# socket.net
KiCad netlist of a schematic drawn in Altium Designer
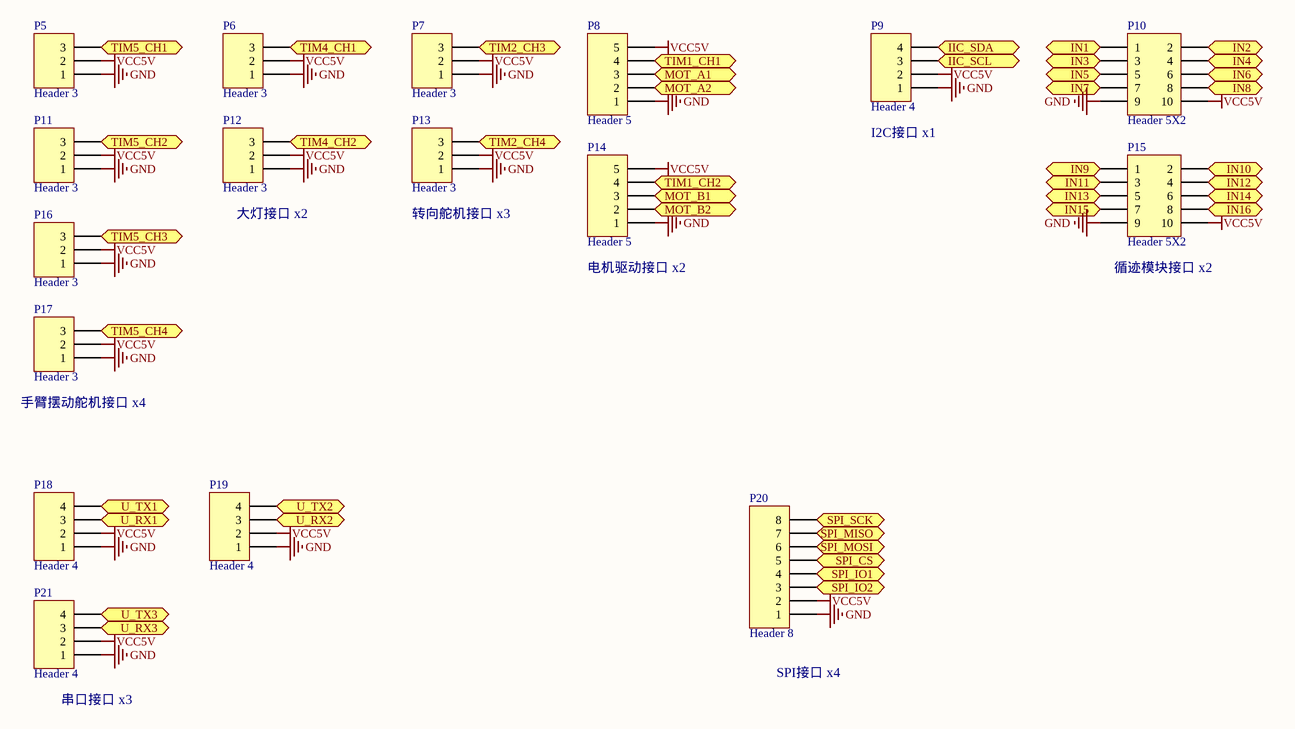
[diagram p0: socket.SchDoc]

(export (version "E")
  (design (tool "Eeschema 10.0.6"))
  (components
    (comp (ref "P5")
      (value "Header 3")
      (footprint "HDR1X3")
      (description "Header, 3-Pin")
      (fields (field (name "PUBLISHER") "Altium Limited"))
      (libsource (lib "Miscellaneous Connectors") (part "Header 3"))
    )
    (comp (ref "P6")
      (value "Header 3")
      (footprint "HDR1X3")
      (description "Header, 3-Pin")
      (fields (field (name "PUBLISHER") "Altium Limited"))
      (libsource (lib "Miscellaneous Connectors") (part "Header 3"))
    )
    (comp (ref "P7")
      (value "Header 3")
      (footprint "HDR1X3")
      (description "Header, 3-Pin")
      (fields (field (name "PUBLISHER") "Altium Limited"))
      (libsource (lib "Miscellaneous Connectors") (part "Header 3"))
    )
    (comp (ref "P8")
      (value "Header 5")
      (footprint "HDR1X5")
      (description "Header, 5-Pin")
      (fields (field (name "PUBLISHER") "Altium Limited"))
      (libsource (lib "Miscellaneous Connectors") (part "Header 5"))
    )
    (comp (ref "P9")
      (value "Header 4")
      (footprint "HDR1X4")
      (description "Header, 4-Pin")
      (fields (field (name "PUBLISHER") "Altium Limited"))
      (libsource (lib "Miscellaneous Connectors") (part "Header 4"))
    )
    (comp (ref "P10")
      (value "Header 5X2")
      (footprint "HDR2X5")
      (description "Header, 5-Pin, Dual row")
      (fields (field (name "PUBLISHER") "Altium Limited"))
      (libsource (lib "Miscellaneous Connectors") (part "Header 5X2"))
    )
    (comp (ref "P11")
      (value "Header 3")
      (footprint "HDR1X3")
      (description "Header, 3-Pin")
      (fields (field (name "PUBLISHER") "Altium Limited"))
      (libsource (lib "Miscellaneous Connectors") (part "Header 3"))
    )
    (comp (ref "P12")
      (value "Header 3")
      (footprint "HDR1X3")
      (description "Header, 3-Pin")
      (fields (field (name "PUBLISHER") "Altium Limited"))
      (libsource (lib "Miscellaneous Connectors") (part "Header 3"))
    )
    (comp (ref "P13")
      (value "Header 3")
      (footprint "HDR1X3")
      (description "Header, 3-Pin")
      (fields (field (name "PUBLISHER") "Altium Limited"))
      (libsource (lib "Miscellaneous Connectors") (part "Header 3"))
    )
    (comp (ref "P14")
      (value "Header 5")
      (footprint "HDR1X5")
      (description "Header, 5-Pin")
      (fields (field (name "PUBLISHER") "Altium Limited"))
      (libsource (lib "Miscellaneous Connectors") (part "Header 5"))
    )
    (comp (ref "P15")
      (value "Header 5X2")
      (footprint "HDR2X5")
      (description "Header, 5-Pin, Dual row")
      (fields (field (name "PUBLISHER") "Altium Limited"))
      (libsource (lib "Miscellaneous Connectors") (part "Header 5X2"))
    )
    (comp (ref "P16")
      (value "Header 3")
      (footprint "HDR1X3")
      (description "Header, 3-Pin")
      (fields (field (name "PUBLISHER") "Altium Limited"))
      (libsource (lib "Miscellaneous Connectors") (part "Header 3"))
    )
    (comp (ref "P17")
      (value "Header 3")
      (footprint "HDR1X3")
      (description "Header, 3-Pin")
      (fields (field (name "PUBLISHER") "Altium Limited"))
      (libsource (lib "Miscellaneous Connectors") (part "Header 3"))
    )
    (comp (ref "P18")
      (value "Header 4")
      (footprint "HDR1X4")
      (description "Header, 4-Pin")
      (fields (field (name "PUBLISHER") "Altium Limited"))
      (libsource (lib "Miscellaneous Connectors") (part "Header 4"))
    )
    (comp (ref "P19")
      (value "Header 4")
      (footprint "HDR1X4")
      (description "Header, 4-Pin")
      (fields (field (name "PUBLISHER") "Altium Limited"))
      (libsource (lib "Miscellaneous Connectors") (part "Header 4"))
    )
    (comp (ref "P20")
      (value "Header 8")
      (footprint "HDR1X8")
      (description "Header, 8-Pin")
      (fields (field (name "PUBLISHER") "Altium Limited"))
      (libsource (lib "Miscellaneous Connectors") (part "Header 8"))
    )
    (comp (ref "P21")
      (value "Header 4")
      (footprint "HDR1X4")
      (description "Header, 4-Pin")
      (fields (field (name "PUBLISHER") "Altium Limited"))
      (libsource (lib "Miscellaneous Connectors") (part "Header 4"))
    )
  )
  (nets
    (net (code "1") (name "/IIC_SCL") (class "Default")
      (node (ref "P9") (pin "3") (pinfunction "3_3") (pintype "passive"))
    )
    (net (code "2") (name "/IIC_SDA") (class "Default")
      (node (ref "P9") (pin "4") (pinfunction "4_4") (pintype "passive"))
    )
    (net (code "3") (name "/IN1") (class "Default")
      (node (ref "P10") (pin "1") (pinfunction "1_1") (pintype "passive"))
    )
    (net (code "4") (name "/IN2") (class "Default")
      (node (ref "P10") (pin "2") (pinfunction "2_2") (pintype "passive"))
    )
    (net (code "5") (name "/IN3") (class "Default")
      (node (ref "P10") (pin "3") (pinfunction "3_3") (pintype "passive"))
    )
    (net (code "6") (name "/IN4") (class "Default")
      (node (ref "P10") (pin "4") (pinfunction "4_4") (pintype "passive"))
    )
    (net (code "7") (name "/IN5") (class "Default")
      (node (ref "P10") (pin "5") (pinfunction "5_5") (pintype "passive"))
    )
    (net (code "8") (name "/IN6") (class "Default")
      (node (ref "P10") (pin "6") (pinfunction "6_6") (pintype "passive"))
    )
    (net (code "9") (name "/IN7") (class "Default")
      (node (ref "P10") (pin "7") (pinfunction "7_7") (pintype "passive"))
    )
    (net (code "10") (name "/IN8") (class "Default")
      (node (ref "P10") (pin "8") (pinfunction "8_8") (pintype "passive"))
    )
    (net (code "11") (name "/IN9") (class "Default")
      (node (ref "P15") (pin "1") (pinfunction "1_1") (pintype "passive"))
    )
    (net (code "12") (name "/IN10") (class "Default")
      (node (ref "P15") (pin "2") (pinfunction "2_2") (pintype "passive"))
    )
    (net (code "13") (name "/IN11") (class "Default")
      (node (ref "P15") (pin "3") (pinfunction "3_3") (pintype "passive"))
    )
    (net (code "14") (name "/IN12") (class "Default")
      (node (ref "P15") (pin "4") (pinfunction "4_4") (pintype "passive"))
    )
    (net (code "15") (name "/IN13") (class "Default")
      (node (ref "P15") (pin "5") (pinfunction "5_5") (pintype "passive"))
    )
    (net (code "16") (name "/IN14") (class "Default")
      (node (ref "P15") (pin "6") (pinfunction "6_6") (pintype "passive"))
    )
    (net (code "17") (name "/IN15") (class "Default")
      (node (ref "P15") (pin "7") (pinfunction "7_7") (pintype "passive"))
    )
    (net (code "18") (name "/IN16") (class "Default")
      (node (ref "P15") (pin "8") (pinfunction "8_8") (pintype "passive"))
    )
    (net (code "19") (name "/MOT_A1") (class "Default")
      (node (ref "P8") (pin "3") (pinfunction "3_3") (pintype "passive"))
    )
    (net (code "20") (name "/MOT_A2") (class "Default")
      (node (ref "P8") (pin "2") (pinfunction "2_2") (pintype "passive"))
    )
    (net (code "21") (name "/MOT_B1") (class "Default")
      (node (ref "P14") (pin "3") (pinfunction "3_3") (pintype "passive"))
    )
    (net (code "22") (name "/MOT_B2") (class "Default")
      (node (ref "P14") (pin "2") (pinfunction "2_2") (pintype "passive"))
    )
    (net (code "23") (name "/SPI_CS") (class "Default")
      (node (ref "P20") (pin "5") (pinfunction "5_5") (pintype "passive"))
    )
    (net (code "24") (name "/SPI_IO1") (class "Default")
      (node (ref "P20") (pin "4") (pinfunction "4_4") (pintype "passive"))
    )
    (net (code "25") (name "/SPI_IO2") (class "Default")
      (node (ref "P20") (pin "3") (pinfunction "3_3") (pintype "passive"))
    )
    (net (code "26") (name "/SPI_MISO") (class "Default")
      (node (ref "P20") (pin "7") (pinfunction "7_7") (pintype "passive"))
    )
    (net (code "27") (name "/SPI_MOSI") (class "Default")
      (node (ref "P20") (pin "6") (pinfunction "6_6") (pintype "passive"))
    )
    (net (code "28") (name "/SPI_SCK") (class "Default")
      (node (ref "P20") (pin "8") (pinfunction "8_8") (pintype "passive"))
    )
    (net (code "29") (name "/TIM1_CH1") (class "Default")
      (node (ref "P8") (pin "4") (pinfunction "4_4") (pintype "passive"))
    )
    (net (code "30") (name "/TIM1_CH2") (class "Default")
      (node (ref "P14") (pin "4") (pinfunction "4_4") (pintype "passive"))
    )
    (net (code "31") (name "/TIM2_CH3") (class "Default")
      (node (ref "P7") (pin "3") (pinfunction "3_3") (pintype "passive"))
    )
    (net (code "32") (name "/TIM2_CH4") (class "Default")
      (node (ref "P13") (pin "3") (pinfunction "3_3") (pintype "passive"))
    )
    (net (code "33") (name "/TIM4_CH1") (class "Default")
      (node (ref "P6") (pin "3") (pinfunction "3_3") (pintype "passive"))
    )
    (net (code "34") (name "/TIM4_CH2") (class "Default")
      (node (ref "P12") (pin "3") (pinfunction "3_3") (pintype "passive"))
    )
    (net (code "35") (name "/TIM5_CH1") (class "Default")
      (node (ref "P5") (pin "3") (pinfunction "3_3") (pintype "passive"))
    )
    (net (code "36") (name "/TIM5_CH2") (class "Default")
      (node (ref "P11") (pin "3") (pinfunction "3_3") (pintype "passive"))
    )
    (net (code "37") (name "/TIM5_CH3") (class "Default")
      (node (ref "P16") (pin "3") (pinfunction "3_3") (pintype "passive"))
    )
    (net (code "38") (name "/TIM5_CH4") (class "Default")
      (node (ref "P17") (pin "3") (pinfunction "3_3") (pintype "passive"))
    )
    (net (code "39") (name "/U_RX1") (class "Default")
      (node (ref "P18") (pin "3") (pinfunction "3_3") (pintype "passive"))
    )
    (net (code "40") (name "/U_RX2") (class "Default")
      (node (ref "P19") (pin "3") (pinfunction "3_3") (pintype "passive"))
    )
    (net (code "41") (name "/U_RX3") (class "Default")
      (node (ref "P21") (pin "3") (pinfunction "3_3") (pintype "passive"))
    )
    (net (code "42") (name "/U_TX1") (class "Default")
      (node (ref "P18") (pin "4") (pinfunction "4_4") (pintype "passive"))
    )
    (net (code "43") (name "/U_TX2") (class "Default")
      (node (ref "P19") (pin "4") (pinfunction "4_4") (pintype "passive"))
    )
    (net (code "44") (name "/U_TX3") (class "Default")
      (node (ref "P21") (pin "4") (pinfunction "4_4") (pintype "passive"))
    )
    (net (code "45") (name "GND") (class "Default")
      (node (ref "P10") (pin "9") (pinfunction "9_9") (pintype "passive"))
      (node (ref "P11") (pin "1") (pinfunction "1_1") (pintype "passive"))
      (node (ref "P12") (pin "1") (pinfunction "1_1") (pintype "passive"))
      (node (ref "P13") (pin "1") (pinfunction "1_1") (pintype "passive"))
      (node (ref "P14") (pin "1") (pinfunction "1_1") (pintype "passive"))
      (node (ref "P15") (pin "9") (pinfunction "9_9") (pintype "passive"))
      (node (ref "P16") (pin "1") (pinfunction "1_1") (pintype "passive"))
      (node (ref "P17") (pin "1") (pinfunction "1_1") (pintype "passive"))
      (node (ref "P18") (pin "1") (pinfunction "1_1") (pintype "passive"))
      (node (ref "P19") (pin "1") (pinfunction "1_1") (pintype "passive"))
      (node (ref "P20") (pin "1") (pinfunction "1_1") (pintype "passive"))
      (node (ref "P21") (pin "1") (pinfunction "1_1") (pintype "passive"))
      (node (ref "P5") (pin "1") (pinfunction "1_1") (pintype "passive"))
      (node (ref "P6") (pin "1") (pinfunction "1_1") (pintype "passive"))
      (node (ref "P7") (pin "1") (pinfunction "1_1") (pintype "passive"))
      (node (ref "P8") (pin "1") (pinfunction "1_1") (pintype "passive"))
      (node (ref "P9") (pin "1") (pinfunction "1_1") (pintype "passive"))
    )
    (net (code "46") (name "VCC5V") (class "Default")
      (node (ref "P10") (pin "10") (pinfunction "10_10") (pintype "passive"))
      (node (ref "P11") (pin "2") (pinfunction "2_2") (pintype "passive"))
      (node (ref "P12") (pin "2") (pinfunction "2_2") (pintype "passive"))
      (node (ref "P13") (pin "2") (pinfunction "2_2") (pintype "passive"))
      (node (ref "P14") (pin "5") (pinfunction "5_5") (pintype "passive"))
      (node (ref "P15") (pin "10") (pinfunction "10_10") (pintype "passive"))
      (node (ref "P16") (pin "2") (pinfunction "2_2") (pintype "passive"))
      (node (ref "P17") (pin "2") (pinfunction "2_2") (pintype "passive"))
      (node (ref "P18") (pin "2") (pinfunction "2_2") (pintype "passive"))
      (node (ref "P19") (pin "2") (pinfunction "2_2") (pintype "passive"))
      (node (ref "P20") (pin "2") (pinfunction "2_2") (pintype "passive"))
      (node (ref "P21") (pin "2") (pinfunction "2_2") (pintype "passive"))
      (node (ref "P5") (pin "2") (pinfunction "2_2") (pintype "passive"))
      (node (ref "P6") (pin "2") (pinfunction "2_2") (pintype "passive"))
      (node (ref "P7") (pin "2") (pinfunction "2_2") (pintype "passive"))
      (node (ref "P8") (pin "5") (pinfunction "5_5") (pintype "passive"))
      (node (ref "P9") (pin "2") (pinfunction "2_2") (pintype "passive"))
    )
  )
)
